# RPE_Schematic.net
KiCad netlist of a schematic drawn in Altium Designer
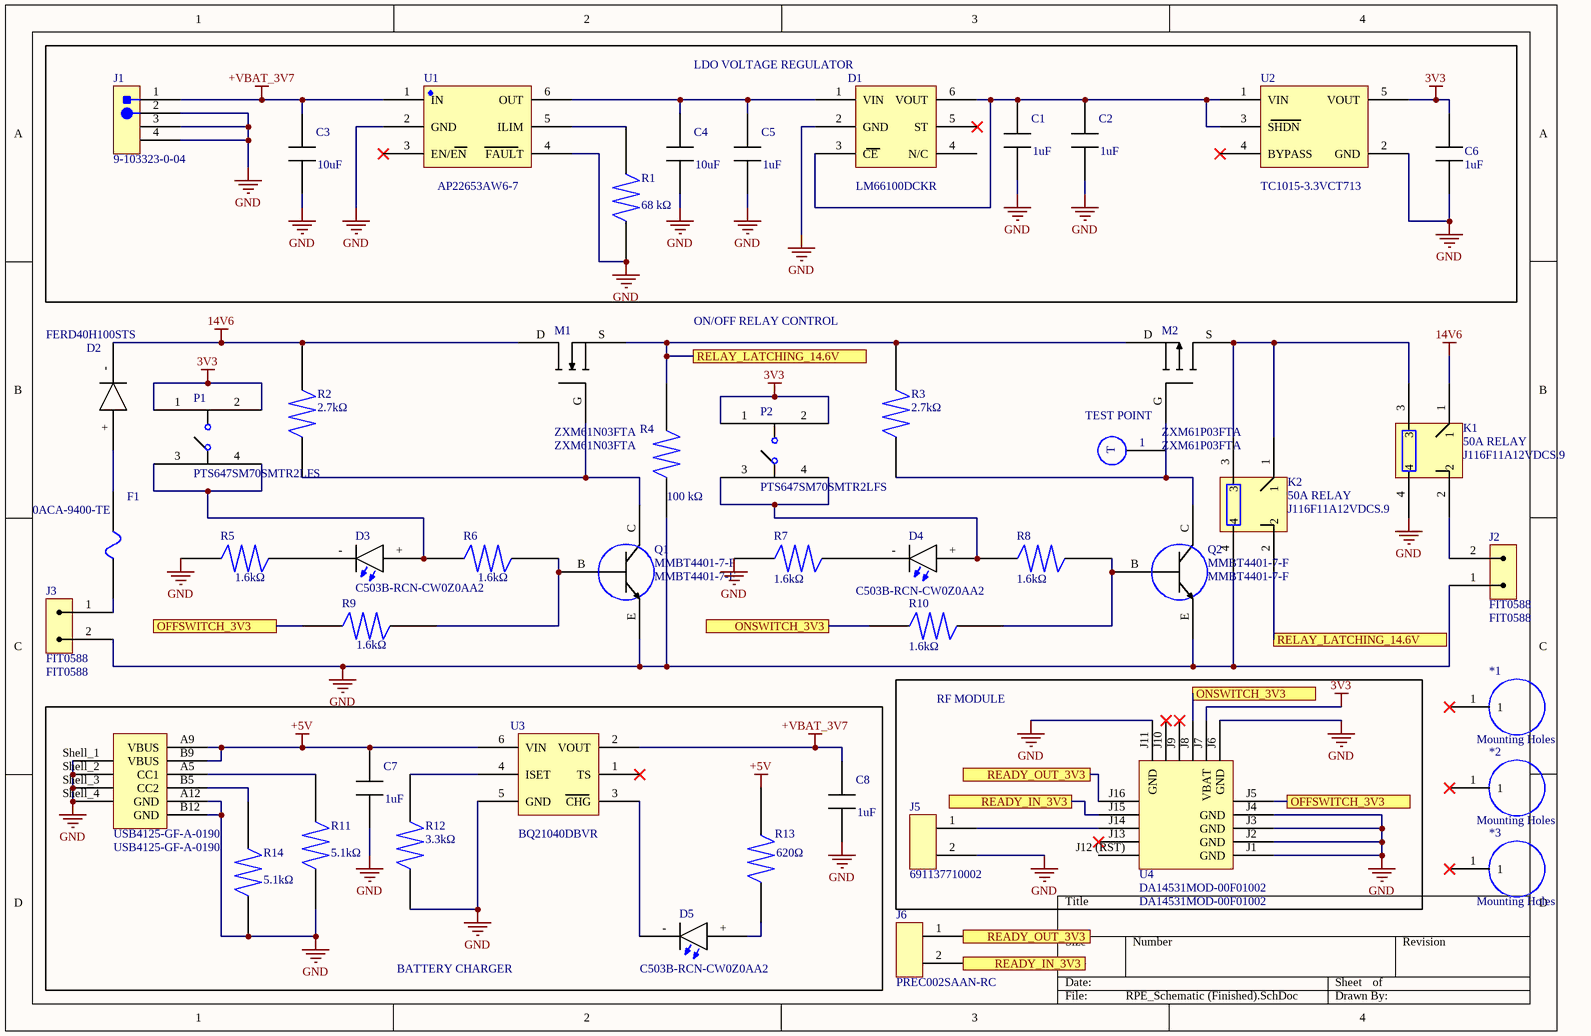
[diagram p0: RPE_Schematic (Finished).SchDoc]

(export (version "E")
  (design (tool "Eeschema 10.0.6"))
  (components
    (comp (ref "*1")
      (value "Mounting Holes")
      (footprint "Mounting Holes")
      (libsource (lib "RPE_Sch_Library_Updated") (part "Mounting Holes"))
    )
    (comp (ref "*2")
      (value "Mounting Holes")
      (footprint "Mounting Holes")
      (libsource (lib "RPE_Sch_Library_Updated") (part "Mounting Holes"))
    )
    (comp (ref "*3")
      (value "Mounting Holes")
      (footprint "Mounting Holes")
      (libsource (lib "RPE_Sch_Library_Updated") (part "Mounting Holes"))
    )
    (comp (ref "C1")
      (value "1uF")
      (footprint "CL10B105MO8NNWC")
      (description "SMD Multilayer Ceramic Capacitor, 1 µF, 16 V, 0603 [1608 Metric], ± 20%, X7R, CL Series")
      (fields
        (field (name "MANUFACTURER") "Samsung")
        (field (name "MANUFACTURER PART NUMBER") "CL10B105MO8NNWC")
      )
      (libsource (lib "RPE_Sch_Library_Updated") (part "CL10B105MO8NNWC"))
    )
    (comp (ref "C2")
      (value "1uF")
      (footprint "CL10B105MO8NNWC")
      (description "SMD Multilayer Ceramic Capacitor, 1 µF, 16 V, 0603 [1608 Metric], ± 20%, X7R, CL Series")
      (fields
        (field (name "MANUFACTURER") "Samsung")
        (field (name "MANUFACTURER PART NUMBER") "CL10B105MO8NNWC")
      )
      (libsource (lib "RPE_Sch_Library_Updated") (part "CL10B105MO8NNWC"))
    )
    (comp (ref "C3")
      (value "10uF")
      (footprint "GRM188D71A106MA73J")
      (description "Cap 10UF 10VDC X7T 20% SMD 0603 Paper Tape")
      (fields
        (field (name "MANUFACTURER") "Murata")
        (field (name "MANUFACTURER PART NUMBER") "GRM188D71A106MA73J")
      )
      (libsource (lib "RPE_Sch_Library_Updated") (part "GRM188D71A106MA73J"))
    )
    (comp (ref "C4")
      (value "10uF")
      (footprint "GRM188D71A106MA73J")
      (description "Cap 10UF 10VDC X7T 20% SMD 0603 Paper Tape")
      (fields
        (field (name "MANUFACTURER") "Murata")
        (field (name "MANUFACTURER PART NUMBER") "GRM188D71A106MA73J")
      )
      (libsource (lib "RPE_Sch_Library_Updated") (part "GRM188D71A106MA73J"))
    )
    (comp (ref "C5")
      (value "1uF")
      (footprint "CL10B105MO8NNWC")
      (description "SMD Multilayer Ceramic Capacitor, 1 µF, 16 V, 0603 [1608 Metric], ± 20%, X7R, CL Series")
      (fields
        (field (name "MANUFACTURER") "Samsung")
        (field (name "MANUFACTURER PART NUMBER") "CL10B105MO8NNWC")
      )
      (libsource (lib "RPE_Sch_Library_Updated") (part "CL10B105MO8NNWC"))
    )
    (comp (ref "C6")
      (value "1uF")
      (footprint "CL10B105MO8NNWC")
      (description "SMD Multilayer Ceramic Capacitor, 1 µF, 16 V, 0603 [1608 Metric], ± 20%, X7R, CL Series")
      (fields
        (field (name "MANUFACTURER") "Samsung")
        (field (name "MANUFACTURER PART NUMBER") "CL10B105MO8NNWC")
      )
      (libsource (lib "RPE_Sch_Library_Updated") (part "CL10B105MO8NNWC"))
    )
    (comp (ref "C7")
      (value "1uF")
      (footprint "CL10B105MO8NNWC")
      (description "SMD Multilayer Ceramic Capacitor, 1 µF, 16 V, 0603 [1608 Metric], ± 20%, X7R, CL Series")
      (fields
        (field (name "MANUFACTURER") "Samsung")
        (field (name "MANUFACTURER PART NUMBER") "CL10B105MO8NNWC")
      )
      (libsource (lib "RPE_Sch_Library_Updated") (part "CL10B105MO8NNWC"))
    )
    (comp (ref "C8")
      (value "1uF")
      (footprint "CL10B105MO8NNWC")
      (description "SMD Multilayer Ceramic Capacitor, 1 µF, 16 V, 0603 [1608 Metric], ± 20%, X7R, CL Series")
      (fields
        (field (name "MANUFACTURER") "Samsung")
        (field (name "MANUFACTURER PART NUMBER") "CL10B105MO8NNWC")
      )
      (libsource (lib "RPE_Sch_Library_Updated") (part "CL10B105MO8NNWC"))
    )
    (comp (ref "D1")
      (value "*")
      (footprint "LM66100DCKR")
      (description "1.5-V to 5.5-V, 1.5-A, 0.5-uA IQ ideal diode with Integrated FET 6-SC70 -40 to 105")
      (fields
        (field (name "MANUFACTURER") "Texas Instruments")
        (field (name "MANUFACTURER PART NUMBER") "LM66100DCKR")
      )
      (libsource (lib "RPE_Sch_Library_Updated") (part "LM66100DCKR"))
    )
    (comp (ref "D2")
      (value "100V DIODE")
      (footprint "FERD40H100STS")
      (description "FERD40H100 Series 100 V 40 A Field Effect Rectifier Diode - TO-220AB")
      (fields
        (field (name "MANUFACTURER") "STMicroelectronics")
        (field (name "MANUFACTURER PART NUMBER") "FERD40H100STS")
      )
      (libsource (lib "RPE_Sch_Library_Updated") (part "FERD40H100STS"))
    )
    (comp (ref "D3")
      (value "RED THROUGH HOLE LED")
      (footprint "C503B-RCN-CW0Z0AA2")
      (description "CREE - C503B-RCN-CW0Z0AA2 - LED, Red, Through Hole, T-1 3/4 (5mm), 20 mA, 2.1 V, 624 nm")
      (fields
        (field (name "MANUFACTURER") "Cree")
        (field (name "MANUFACTURER PART NUMBER") "C503B-RCN-CW0Z0AA2")
      )
      (libsource (lib "RPE_Sch_Library_Updated") (part "C503B-RCN-CW0Z0AA2"))
    )
    (comp (ref "D4")
      (value "RED THROUGH HOLE LED")
      (footprint "C503B-RCN-CW0Z0AA2")
      (description "CREE - C503B-RCN-CW0Z0AA2 - LED, Red, Through Hole, T-1 3/4 (5mm), 20 mA, 2.1 V, 624 nm")
      (fields
        (field (name "MANUFACTURER") "Cree")
        (field (name "MANUFACTURER PART NUMBER") "C503B-RCN-CW0Z0AA2")
      )
      (libsource (lib "RPE_Sch_Library_Updated") (part "C503B-RCN-CW0Z0AA2"))
    )
    (comp (ref "D5")
      (value "RED THROUGH HOLE LED")
      (footprint "C503B-RCN-CW0Z0AA2")
      (description "CREE - C503B-RCN-CW0Z0AA2 - LED, Red, Through Hole, T-1 3/4 (5mm), 20 mA, 2.1 V, 624 nm")
      (fields
        (field (name "MANUFACTURER") "Cree")
        (field (name "MANUFACTURER PART NUMBER") "C503B-RCN-CW0Z0AA2")
      )
      (libsource (lib "RPE_Sch_Library_Updated") (part "C503B-RCN-CW0Z0AA2"))
    )
    (comp (ref "F1")
      (value "40A FUSE")
      (footprint "0ACA-9400-TE")
      (description "Bel Fuse, Internal Part #: 0ACA-9400-TE 40A FUSE")
      (fields (field (name "MANUFACTURER") "Bel") (field (name "MANUFACTURER PART NUMBER") "0ACA-9400-TE"))
      (libsource (lib "RPE_Sch_Library_Updated") (part "0ACA-9400-TE"))
    )
    (comp (ref "J1")
      (value "9-103323-0-04")
      (footprint "9-103323-0-04")
      (description "CONN HEADR BRKWAY .100 04POS R/A 4 PIN HEADER")
      (fields (field (name "MANUFACTURER") "TE Connectivity"))
      (libsource (lib "RPE_Sch_Library_Updated") (part "9-103323-0-04"))
    )
    (comp (ref "J2")
      (value "FIT0588")
      (footprint "FIT0588")
      (description "High Quality Gold Plated Male and Female Bullet Connector")
      (fields (field (name "MANUFACTURER") "DFRobot") (field (name "MANUFACTURER PART NUMBER") "FIT0588"))
      (libsource (lib "RPE_Sch_Library_Updated") (part "FIT0588"))
    )
    (comp (ref "J3")
      (value "FIT0588")
      (footprint "FIT0588")
      (description "High Quality Gold Plated Male and Female Bullet Connector")
      (fields (field (name "MANUFACTURER") "DFRobot") (field (name "MANUFACTURER PART NUMBER") "FIT0588"))
      (libsource (lib "") (part "FIT0588_1"))
    )
    (comp (ref "J4")
      (value "USB4125-GF-A-0190")
      (footprint "USB4125-GF-A")
      (description "USB Connector, 24 Contact(s), Female, Right Angle, Solder Terminal, Locking, Receptacle")
      (fields
        (field (name "MANUFACTURER") "Global Connector Technology")
        (field (name "MANUFACTURER PART NUMBER") "USB4125-GF-A-0190")
      )
      (libsource (lib "RPE_Sch_Library_Updated") (part "USB4125-GF-A-0190"))
    )
    (comp (ref "J5")
      (value "691137710002")
      (footprint "691137710002")
      (description "Series 1377 - 5.00 mm Horizontal Entry with Pressure Clamp WR-TBL, 2 pin")
      (fields
        (field (name "MANUFACTURER") "Wurth Electronics")
        (field (name "VOLTAGE") "300V")
        (field (name "MANUFACTURER PART NUMBER") "691137710002")
      )
      (libsource (lib "RPE_Sch_Library_Updated") (part "691137710002"))
    )
    (comp (ref "J6")
      (value "PREC002SAAN-RC")
      (footprint "PREC002SAAN-RC")
      (description "CONN HEADER VERT 2POS 2.54MM")
      (libsource (lib "RPE_Sch_Library_Updated") (part "PREC002SAAN-RC"))
    )
    (comp (ref "K1")
      (value "50A RELAY")
      (footprint "J116F11A12VDCS.9")
      (description "Relay Gen Purpose SPST 50A 12V")
      (fields
        (field (name "MANUFACTURER") "CIT Relay & Switch")
        (field (name "MANUFACTURER PART NUMBER") "J116F11A12VDCS.9")
      )
      (libsource (lib "RPE_Sch_Library_Updated") (part "J116F11A12VDCS.9"))
    )
    (comp (ref "K2")
      (value "50A RELAY")
      (footprint "J116F11A12VDCS.9")
      (description "Relay Gen Purpose SPST 50A 12V")
      (fields
        (field (name "MANUFACTURER") "CIT Relay & Switch")
        (field (name "MANUFACTURER PART NUMBER") "J116F11A12VDCS.9")
      )
      (libsource (lib "RPE_Sch_Library_Updated") (part "J116F11A12VDCS.9"))
    )
    (comp (ref "M1")
      (value "ZXM61N03FTA")
      (footprint "ZXM61N03FTA")
      (description "N-Channel 30V 1.4A (Ta) 625mW (Ta) Surface Mount SOT-23-3")
      (fields
        (field (name "MANUFACTURER") "Diodes Zetex")
        (field (name "MANUFACTURER PART NUMBER") "ZXM61N03FTA")
      )
      (libsource (lib "RPE_Sch_Library_Updated") (part "ZXM61N03FTA"))
    )
    (comp (ref "M2")
      (value "ZXM61P03FTA")
      (footprint "ZXM61P03FTA")
      (description "ZXM61P03F 30 V 0.35 Ohm P-Channel Enhancement Mode Vertical DMOS FET - SOT-23")
      (fields
        (field (name "MANUFACTURER") "Diodes Zetex")
        (field (name "MANUFACTURER PART NUMBER") "ZXM61P03FTA")
      )
      (libsource (lib "RPE_Sch_Library_Updated") (part "ZXM61P03FTA"))
    )
    (comp (ref "P1")
      (value "*")
      (footprint "PTS 647 SK50 SMTR2 LFS")
      (description "Switch Tactile N.O. SPST Round Button Gull Wing 0.05A 12VDC 100000Cycles 1.77N SMD T/R")
      (fields
        (field (name "MANUFACTURER") "ITT C&K")
        (field (name "MANUFACTURER PART NUMBER") "PTS647SM70SMTR2LFS")
      )
      (libsource (lib "RPE_Sch_Library_Updated") (part "PTS647SM70SMTR2LFS"))
    )
    (comp (ref "P2")
      (value "*")
      (footprint "PTS 647 SK50 SMTR2 LFS")
      (description "Switch Tactile N.O. SPST Round Button Gull Wing 0.05A 12VDC 100000Cycles 1.77N SMD T/R")
      (fields
        (field (name "MANUFACTURER") "ITT C&K")
        (field (name "MANUFACTURER PART NUMBER") "PTS647SM70SMTR2LFS")
      )
      (libsource (lib "RPE_Sch_Library_Updated") (part "PTS647SM70SMTR2LFS"))
    )
    (comp (ref "Q1")
      (value "MMBT4401-7-F")
      (footprint "MMBT4401-13-F")
      (description "Bipolar Transistors - 40V NPN SMALL SIGNAL TRANSISTOR IN SOT23 package")
      (fields
        (field (name "MANUFACTURER") "Diodes Zetex")
        (field (name "MANUFACTURER PART NUMBER") "MMBT4401-7-F")
      )
      (libsource (lib "RPE_Sch_Library_Updated") (part "MMBT4401-7-F"))
    )
    (comp (ref "Q2")
      (value "MMBT4401-7-F")
      (footprint "MMBT4401-13-F")
      (description "Bipolar Transistors - 40V NPN SMALL SIGNAL TRANSISTOR IN SOT23 package")
      (fields
        (field (name "MANUFACTURER") "Diodes Zetex")
        (field (name "MANUFACTURER PART NUMBER") "MMBT4401-7-F")
      )
      (libsource (lib "RPE_Sch_Library_Updated") (part "MMBT4401-7-F"))
    )
    (comp (ref "R1")
      (value "68 kΩ")
      (footprint "RMCF0603FT68K0")
      (description "Res Thick Film 0603 68K Ohm 1% 0.1W(1/10W) ±100ppm/C Pad SMD T/R Automotive AEC-Q200")
      (fields
        (field (name "MANUFACTURER") "Stackpole Electronics")
        (field (name "MANUFACTURER PART NUMBER") "RMCF0603FT68K0")
      )
      (libsource (lib "RPE_Sch_Library_Updated") (part "RMCF0603FT68K0"))
    )
    (comp (ref "R2")
      (value "2.7kΩ")
      (footprint "CR0603-FX-2701ELF")
      (description "SMD Chip Resistor, 2.7 kOhm, ± 1%, 100 mW, 0603 [1608 Metric], Thick Film, General Purpose")
      (fields
        (field (name "MANUFACTURER") "Bourns")
        (field (name "MANUFACTURER PART NUMBER") "CR0603-FX-2701ELF")
      )
      (libsource (lib "RPE_Sch_Library_Updated") (part "CR0603-FX-2701ELF"))
    )
    (comp (ref "R3")
      (value "2.7kΩ")
      (footprint "CR0603-FX-2701ELF")
      (description "SMD Chip Resistor, 2.7 kOhm, ± 1%, 100 mW, 0603 [1608 Metric], Thick Film, General Purpose")
      (fields
        (field (name "MANUFACTURER") "Bourns")
        (field (name "MANUFACTURER PART NUMBER") "CR0603-FX-2701ELF")
      )
      (libsource (lib "RPE_Sch_Library_Updated") (part "CR0603-FX-2701ELF"))
    )
    (comp (ref "R4")
      (value "100 kΩ")
      (footprint "CR0603FB100KS1")
      (description "100 kΩ Resistor")
      (libsource (lib "RPE_Sch_Library_Updated") (part "CR0603FB100KS1"))
    )
    (comp (ref "R5")
      (value "1.6kΩ")
      (footprint "SG73P1JTTD1601F")
      (description "Res, 1K6, 1%, 0.2W, 0603 Rohs Compliant: Yes")
      (fields
        (field (name "MANUFACTURER") "KOA Speer")
        (field (name "MANUFACTURER PART NUMBER") "SG73P1JTTD1601F")
      )
      (libsource (lib "RPE_Sch_Library_Updated") (part "SG73P1JTTD1601F"))
    )
    (comp (ref "R6")
      (value "1.6kΩ")
      (footprint "SG73P1JTTD1601F")
      (description "Res, 1K6, 1%, 0.2W, 0603 Rohs Compliant: Yes")
      (fields
        (field (name "MANUFACTURER") "KOA Speer")
        (field (name "MANUFACTURER PART NUMBER") "SG73P1JTTD1601F")
      )
      (libsource (lib "RPE_Sch_Library_Updated") (part "SG73P1JTTD1601F"))
    )
    (comp (ref "R7")
      (value "1.6kΩ")
      (footprint "SG73P1JTTD1601F")
      (description "Res, 1K6, 1%, 0.2W, 0603 Rohs Compliant: Yes")
      (fields
        (field (name "MANUFACTURER") "KOA Speer")
        (field (name "MANUFACTURER PART NUMBER") "SG73P1JTTD1601F")
      )
      (libsource (lib "RPE_Sch_Library_Updated") (part "SG73P1JTTD1601F"))
    )
    (comp (ref "R8")
      (value "1.6kΩ")
      (footprint "SG73P1JTTD1601F")
      (description "Res, 1K6, 1%, 0.2W, 0603 Rohs Compliant: Yes")
      (fields
        (field (name "MANUFACTURER") "KOA Speer")
        (field (name "MANUFACTURER PART NUMBER") "SG73P1JTTD1601F")
      )
      (libsource (lib "RPE_Sch_Library_Updated") (part "SG73P1JTTD1601F"))
    )
    (comp (ref "R9")
      (value "1.6kΩ")
      (footprint "SG73P1JTTD1601F")
      (description "Res, 1K6, 1%, 0.2W, 0603 Rohs Compliant: Yes")
      (fields
        (field (name "MANUFACTURER") "KOA Speer")
        (field (name "MANUFACTURER PART NUMBER") "SG73P1JTTD1601F")
      )
      (libsource (lib "RPE_Sch_Library_Updated") (part "SG73P1JTTD1601F"))
    )
    (comp (ref "R10")
      (value "1.6kΩ")
      (footprint "SG73P1JTTD1601F")
      (description "Res, 1K6, 1%, 0.2W, 0603 Rohs Compliant: Yes")
      (fields
        (field (name "MANUFACTURER") "KOA Speer")
        (field (name "MANUFACTURER PART NUMBER") "SG73P1JTTD1601F")
      )
      (libsource (lib "RPE_Sch_Library_Updated") (part "SG73P1JTTD1601F"))
    )
    (comp (ref "R11")
      (value "5.1kΩ")
      (footprint "RC0603FR-075K1L")
      (description "SMD Chip Resistor, 5.1 kOhm, ± 1%, 100 mW, 0603 [1608 Metric], Thick Film, General Purpose")
      (fields
        (field (name "MANUFACTURER") "Yageo")
        (field (name "MANUFACTURER PART NUMBER") "RC0603FR-075K1L")
      )
      (libsource (lib "RPE_Sch_Library_Updated") (part "RC0603FR-075K1L"))
    )
    (comp (ref "R12")
      (value "3.3kΩ")
      (footprint "RC0603JR-133K3L")
      (description "SMD Chip Resistor, 3.3 kOhm, ± 1%, 100 mW, 0603 [1608 Metric], Thick Film, General Purpose")
      (fields
        (field (name "MANUFACTURER") "Yageo")
        (field (name "MANUFACTURER PART NUMBER") "RC0603FR-133K3L")
      )
      (libsource (lib "RPE_Sch_Library_Updated") (part "RC0603FR-133K3L"))
    )
    (comp (ref "R13")
      (value "620Ω")
      (footprint "RMCF0603FT620R")
      (description "Res Thick Film 0603 620 Ohm 1% 1/10W ±100ppm/°C Molded SMD SMD Paper T/R")
      (fields
        (field (name "MANUFACTURER") "Stackpole Electronics")
        (field (name "MANUFACTURER PART NUMBER") "RMCF0603FT620R")
      )
      (libsource (lib "RPE_Sch_Library_Updated") (part "RMCF0603FT620R"))
    )
    (comp (ref "R14")
      (value "5.1kΩ")
      (footprint "RC0603FR-075K1L")
      (description "SMD Chip Resistor, 5.1 kOhm, ± 1%, 100 mW, 0603 [1608 Metric], Thick Film, General Purpose")
      (fields
        (field (name "MANUFACTURER") "Yageo")
        (field (name "MANUFACTURER PART NUMBER") "RC0603FR-075K1L")
      )
      (libsource (lib "RPE_Sch_Library_Updated") (part "RC0603FR-075K1L"))
    )
    (comp (ref "U1")
      (value "*")
      (footprint "AP22653AW6-7")
      (description "PRECISION ADJUSTABLE CURRENT-LIMITED POWER SWITCHES, -40 to 85°C pF, RoHS")
      (fields (field (name "MANUFACTURER") "Diodes") (field (name "MANUFACTURER PART NUMBER") "AP22653AW6-7"))
      (libsource (lib "RPE_Sch_Library_Updated") (part "AP22653AW6-7"))
    )
    (comp (ref "U2")
      (value "*")
      (footprint "TC1015-3.3VCT713")
      (description "TC1015 Series 100 mA 3.3 V Fixed Output LDO Regulator w/ Shutdown - SOT-23-5")
      (fields
        (field (name "MANUFACTURER") "Microchip")
        (field (name "MANUFACTURER PART NUMBER") "TC1015-3.3VCT713")
      )
      (libsource (lib "RPE_Sch_Library_Updated") (part "TC1015-3.3VCT713"))
    )
    (comp (ref "U3")
      (value "BQ21040DBVR")
      (footprint "BQ21040DBVR")
      (description "IC BAT CHG LI-ION 1 CELL SOT23-6 BATTERY CHARGER")
      (fields
        (field (name "MANUFACTURER") "Texas Instruments")
        (field (name "MANUFACTURER PART NUMBER") "BQ21040DBVR")
      )
      (libsource (lib "RPE_Sch_Library_Updated") (part "BQ21040DBVR"))
    )
    (comp (ref "U4")
      (value "DA14531MOD-00F01002")
      (footprint "DA14531MOD_REN")
      (description "Bluetooth Module, 1MBPS, Bluetooth 5.1 Rohs Compliant: Yes")
      (fields
        (field (name "MANUFACTURER") "Renesas")
        (field (name "MANUFACTURER PART NUMBER") "DA14531MOD-00F01002")
      )
      (libsource (lib "RPE_Sch_Library_Updated") (part "DA14531MOD-00F01002"))
    )
  )
  (nets
    (net (code "1") (name "+5V") (class "Default")
      (node (ref "C7") (pin "2") (pintype "passive"))
      (node (ref "J4") (pin "A9") (pinfunction "VBUS_A9") (pintype "passive"))
      (node (ref "J4") (pin "B9") (pinfunction "VBUS_B9") (pintype "passive"))
      (node (ref "R13") (pin "2") (pintype "passive"))
      (node (ref "U3") (pin "6") (pinfunction "VIN_6") (pintype "passive"))
    )
    (net (code "2") (name "+VBAT_3V7") (class "Default")
      (node (ref "C3") (pin "2") (pintype "passive"))
      (node (ref "C8") (pin "2") (pintype "passive"))
      (node (ref "J1") (pin "1") (pintype "passive"))
      (node (ref "U1") (pin "1") (pinfunction "IN_1") (pintype "passive"))
      (node (ref "U3") (pin "2") (pinfunction "VOUT_2") (pintype "passive"))
    )
    (net (code "3") (name "/OFFSWITCH_3V3") (class "Default")
      (node (ref "R9") (pin "1") (pintype "passive"))
      (node (ref "U4") (pin "J5") (pintype "passive"))
    )
    (net (code "4") (name "/ONSWITCH_3V3") (class "Default")
      (node (ref "R10") (pin "1") (pintype "passive"))
      (node (ref "U4") (pin "J8") (pintype "passive"))
    )
    (net (code "5") (name "/READY_IN_3V3") (class "Default")
      (node (ref "J6") (pin "2") (pintype "passive"))
      (node (ref "U4") (pin "J15") (pintype "passive"))
    )
    (net (code "6") (name "/READY_OUT_3V3") (class "Default")
      (node (ref "J6") (pin "1") (pintype "passive"))
      (node (ref "U4") (pin "J16") (pintype "passive"))
    )
    (net (code "7") (name "/RELAY_LATCHING_14.6V") (class "Default")
      (node (ref "K2") (pin "2") (pinfunction "2_2") (pintype "passive"))
      (node (ref "M1") (pin "S") (pinfunction "S_S") (pintype "passive"))
      (node (ref "M2") (pin "D") (pinfunction "D_D") (pintype "passive"))
      (node (ref "R3") (pin "2") (pintype "passive"))
      (node (ref "R4") (pin "2") (pintype "passive"))
    )
    (net (code "8") (name "3V3") (class "Default")
      (node (ref "C6") (pin "2") (pintype "passive"))
      (node (ref "P1") (pin "1") (pintype "passive"))
      (node (ref "P1") (pin "2") (pintype "passive"))
      (node (ref "P2") (pin "1") (pintype "passive"))
      (node (ref "P2") (pin "2") (pintype "passive"))
      (node (ref "U2") (pin "5") (pinfunction "VOUT_5") (pintype "passive"))
      (node (ref "U4") (pin "J7") (pinfunction "VBAT_J7") (pintype "passive"))
    )
    (net (code "9") (name "14V6") (class "Default")
      (node (ref "D2") (pin "-") (pintype "passive"))
      (node (ref "K1") (pin "1") (pinfunction "1_1") (pintype "passive"))
      (node (ref "M1") (pin "D") (pinfunction "D_D") (pintype "passive"))
      (node (ref "R2") (pin "2") (pintype "passive"))
    )
    (net (code "10") (name "GND") (class "Default")
      (node (ref "C1") (pin "1") (pintype "passive"))
      (node (ref "C2") (pin "1") (pintype "passive"))
      (node (ref "C3") (pin "1") (pintype "passive"))
      (node (ref "C4") (pin "1") (pintype "passive"))
      (node (ref "C5") (pin "1") (pintype "passive"))
      (node (ref "C6") (pin "1") (pintype "passive"))
      (node (ref "C7") (pin "1") (pintype "passive"))
      (node (ref "C8") (pin "1") (pintype "passive"))
      (node (ref "D1") (pin "2") (pinfunction "GND_2") (pintype "passive"))
      (node (ref "J1") (pin "2") (pintype "passive"))
      (node (ref "J1") (pin "3") (pintype "passive"))
      (node (ref "J1") (pin "4") (pintype "passive"))
      (node (ref "J2") (pin "1") (pintype "passive"))
      (node (ref "J3") (pin "2") (pintype "passive"))
      (node (ref "J4") (pin "A12") (pinfunction "GND_A12") (pintype "passive"))
      (node (ref "J4") (pin "B12") (pinfunction "GND_B12") (pintype "passive"))
      (node (ref "J4") (pin "Shell_1") (pintype "passive"))
      (node (ref "J4") (pin "Shell_2") (pintype "passive"))
      (node (ref "J4") (pin "Shell_3") (pintype "passive"))
      (node (ref "J4") (pin "Shell_4") (pintype "passive"))
      (node (ref "J5") (pin "2") (pintype "passive"))
      (node (ref "K1") (pin "4") (pinfunction "4_4") (pintype "passive"))
      (node (ref "K2") (pin "4") (pinfunction "4_4") (pintype "passive"))
      (node (ref "Q1") (pin "E") (pinfunction "E_E") (pintype "passive"))
      (node (ref "Q2") (pin "E") (pinfunction "E_E") (pintype "passive"))
      (node (ref "R1") (pin "1") (pintype "passive"))
      (node (ref "R11") (pin "1") (pintype "passive"))
      (node (ref "R12") (pin "1") (pintype "passive"))
      (node (ref "R14") (pin "1") (pintype "passive"))
      (node (ref "R4") (pin "1") (pintype "passive"))
      (node (ref "R5") (pin "1") (pintype "passive"))
      (node (ref "R7") (pin "1") (pintype "passive"))
      (node (ref "U1") (pin "2") (pinfunction "GND_2") (pintype "passive"))
      (node (ref "U1") (pin "4") (pinfunction "FAULT_4") (pintype "passive"))
      (node (ref "U2") (pin "2") (pinfunction "GND_2") (pintype "passive"))
      (node (ref "U3") (pin "5") (pinfunction "GND_5") (pintype "passive"))
      (node (ref "U4") (pin "J1") (pinfunction "GND_J1") (pintype "passive"))
      (node (ref "U4") (pin "J11") (pinfunction "GND_J11") (pintype "passive"))
      (node (ref "U4") (pin "J2") (pinfunction "GND_J2") (pintype "passive"))
      (node (ref "U4") (pin "J3") (pinfunction "GND_J3") (pintype "passive"))
      (node (ref "U4") (pin "J4") (pinfunction "GND_J4") (pintype "passive"))
      (node (ref "U4") (pin "J6") (pinfunction "GND_J6") (pintype "passive"))
    )
    (net (code "11") (name "Net-(D1-CE)") (class "Default")
      (node (ref "C1") (pin "2") (pintype "passive"))
      (node (ref "C2") (pin "2") (pintype "passive"))
      (node (ref "D1") (pin "3") (pinfunction "CE_3") (pintype "passive"))
      (node (ref "D1") (pin "6") (pinfunction "VOUT_6") (pintype "passive"))
      (node (ref "U2") (pin "1") (pinfunction "VIN_1") (pintype "passive"))
      (node (ref "U2") (pin "3") (pinfunction "SHDN_3") (pintype "passive"))
    )
    (net (code "12") (name "Net-(D1-VIN)") (class "Default")
      (node (ref "C4") (pin "2") (pintype "passive"))
      (node (ref "C5") (pin "2") (pintype "passive"))
      (node (ref "D1") (pin "1") (pinfunction "VIN_1") (pintype "passive"))
      (node (ref "U1") (pin "6") (pinfunction "OUT_6") (pintype "passive"))
    )
    (net (code "13") (name "Net-(D2-Pad+)") (class "Default")
      (node (ref "D2") (pin "+") (pintype "passive"))
      (node (ref "F1") (pin "1") (pintype "passive"))
    )
    (net (code "14") (name "Net-(D3-Pad+)") (class "Default")
      (node (ref "D3") (pin "+") (pintype "passive"))
      (node (ref "P1") (pin "3") (pintype "passive"))
      (node (ref "P1") (pin "4") (pintype "passive"))
      (node (ref "R6") (pin "1") (pintype "passive"))
    )
    (net (code "15") (name "Net-(D3-Pad-)") (class "Default")
      (node (ref "D3") (pin "-") (pintype "passive"))
      (node (ref "R5") (pin "2") (pintype "passive"))
    )
    (net (code "16") (name "Net-(D4-Pad+)") (class "Default")
      (node (ref "D4") (pin "+") (pintype "passive"))
      (node (ref "P2") (pin "3") (pintype "passive"))
      (node (ref "P2") (pin "4") (pintype "passive"))
      (node (ref "R8") (pin "1") (pintype "passive"))
    )
    (net (code "17") (name "Net-(D4-Pad-)") (class "Default")
      (node (ref "D4") (pin "-") (pintype "passive"))
      (node (ref "R7") (pin "2") (pintype "passive"))
    )
    (net (code "18") (name "Net-(D5-Pad+)") (class "Default")
      (node (ref "D5") (pin "+") (pintype "passive"))
      (node (ref "R13") (pin "1") (pintype "passive"))
    )
    (net (code "19") (name "Net-(F1-Pad2)") (class "Default")
      (node (ref "F1") (pin "2") (pintype "passive"))
      (node (ref "J3") (pin "1") (pintype "passive"))
    )
    (net (code "20") (name "Net-(J2-Pad2)") (class "Default")
      (node (ref "J2") (pin "2") (pintype "passive"))
      (node (ref "K1") (pin "2") (pinfunction "2_2") (pintype "passive"))
    )
    (net (code "21") (name "Net-(J4-CC1)") (class "Default")
      (node (ref "J4") (pin "A5") (pinfunction "CC1_A5") (pintype "passive"))
      (node (ref "R11") (pin "2") (pintype "passive"))
    )
    (net (code "22") (name "Net-(J4-CC2)") (class "Default")
      (node (ref "J4") (pin "B5") (pinfunction "CC2_B5") (pintype "passive"))
      (node (ref "R14") (pin "2") (pintype "passive"))
    )
    (net (code "23") (name "Net-(J5-Pad1)") (class "Default")
      (node (ref "J5") (pin "1") (pintype "passive"))
      (node (ref "U4") (pin "J14") (pintype "passive"))
    )
    (net (code "24") (name "Net-(K1-Pad3)") (class "Default")
      (node (ref "K1") (pin "3") (pinfunction "3_3") (pintype "passive"))
      (node (ref "K2") (pin "1") (pinfunction "1_1") (pintype "passive"))
      (node (ref "K2") (pin "3") (pinfunction "3_3") (pintype "passive"))
      (node (ref "M2") (pin "S") (pinfunction "S_S") (pintype "passive"))
    )
    (net (code "25") (name "Net-(M1-PadG)") (class "Default")
      (node (ref "M1") (pin "G") (pinfunction "G_G") (pintype "passive"))
      (node (ref "Q1") (pin "C") (pinfunction "C_C") (pintype "passive"))
      (node (ref "R2") (pin "1") (pintype "passive"))
    )
    (net (code "26") (name "Net-(M2-PadG)") (class "Default")
      (node (ref "M2") (pin "G") (pinfunction "G_G") (pintype "passive"))
      (node (ref "Q2") (pin "C") (pinfunction "C_C") (pintype "passive"))
      (node (ref "R3") (pin "1") (pintype "passive"))
    )
    (net (code "27") (name "Net-(Q1-PadB)") (class "Default")
      (node (ref "Q1") (pin "B") (pinfunction "B_B") (pintype "passive"))
      (node (ref "R6") (pin "2") (pintype "passive"))
      (node (ref "R9") (pin "2") (pintype "passive"))
    )
    (net (code "28") (name "Net-(Q2-PadB)") (class "Default")
      (node (ref "Q2") (pin "B") (pinfunction "B_B") (pintype "passive"))
      (node (ref "R10") (pin "2") (pintype "passive"))
      (node (ref "R8") (pin "2") (pintype "passive"))
    )
    (net (code "29") (name "Net-(U1-ILIM)") (class "Default")
      (node (ref "R1") (pin "2") (pintype "passive"))
      (node (ref "U1") (pin "5") (pinfunction "ILIM_5") (pintype "passive"))
    )
    (net (code "30") (name "Net-(U3-CHG)") (class "Default")
      (node (ref "D5") (pin "-") (pintype "passive"))
      (node (ref "U3") (pin "3") (pinfunction "CHG_3") (pintype "passive"))
    )
    (net (code "31") (name "Net-(U3-ISET)") (class "Default")
      (node (ref "R12") (pin "2") (pintype "passive"))
      (node (ref "U3") (pin "4") (pinfunction "ISET_4") (pintype "passive"))
    )
    (net (code "32") (name "unconnected-(*1-Pad1)") (class "Default")
      (node (ref "*1") (pin "1") (pinfunction "1_1") (pintype "passive+no_connect"))
    )
    (net (code "33") (name "unconnected-(*2-Pad1)") (class "Default")
      (node (ref "*2") (pin "1") (pinfunction "1_1") (pintype "passive+no_connect"))
    )
    (net (code "34") (name "unconnected-(*3-Pad1)") (class "Default")
      (node (ref "*3") (pin "1") (pinfunction "1_1") (pintype "passive+no_connect"))
    )
    (net (code "35") (name "unconnected-(D1-N{slash}C-Pad4)") (class "Default")
      (node (ref "D1") (pin "4") (pinfunction "N/C_4") (pintype "passive"))
    )
    (net (code "36") (name "unconnected-(D1-ST-Pad5)") (class "Default")
      (node (ref "D1") (pin "5") (pinfunction "ST_5") (pintype "passive+no_connect"))
    )
    (net (code "37") (name "unconnected-(U1-EN{slash}EN-Pad3)") (class "Default")
      (node (ref "U1") (pin "3") (pinfunction "EN/EN_3") (pintype "passive+no_connect"))
    )
    (net (code "38") (name "unconnected-(U2-BYPASS-Pad4)") (class "Default")
      (node (ref "U2") (pin "4") (pinfunction "BYPASS_4") (pintype "passive+no_connect"))
    )
    (net (code "39") (name "unconnected-(U3-TS-Pad1)") (class "Default")
      (node (ref "U3") (pin "1") (pinfunction "TS_1") (pintype "passive+no_connect"))
    )
    (net (code "40") (name "unconnected-(U4-PadJ9)") (class "Default")
      (node (ref "U4") (pin "J9") (pintype "passive+no_connect"))
    )
    (net (code "41") (name "unconnected-(U4-PadJ10)") (class "Default")
      (node (ref "U4") (pin "J10") (pintype "passive+no_connect"))
    )
    (net (code "42") (name "unconnected-(U4-PadJ12_(RST))") (class "Default")
      (node (ref "U4") (pin "J12_(RST)") (pintype "passive"))
    )
    (net (code "43") (name "unconnected-(U4-PadJ13)") (class "Default")
      (node (ref "U4") (pin "J13") (pintype "passive+no_connect"))
    )
  )
)
